# stm8-hid.net
KiCad netlist of a schematic drawn in EAGLE
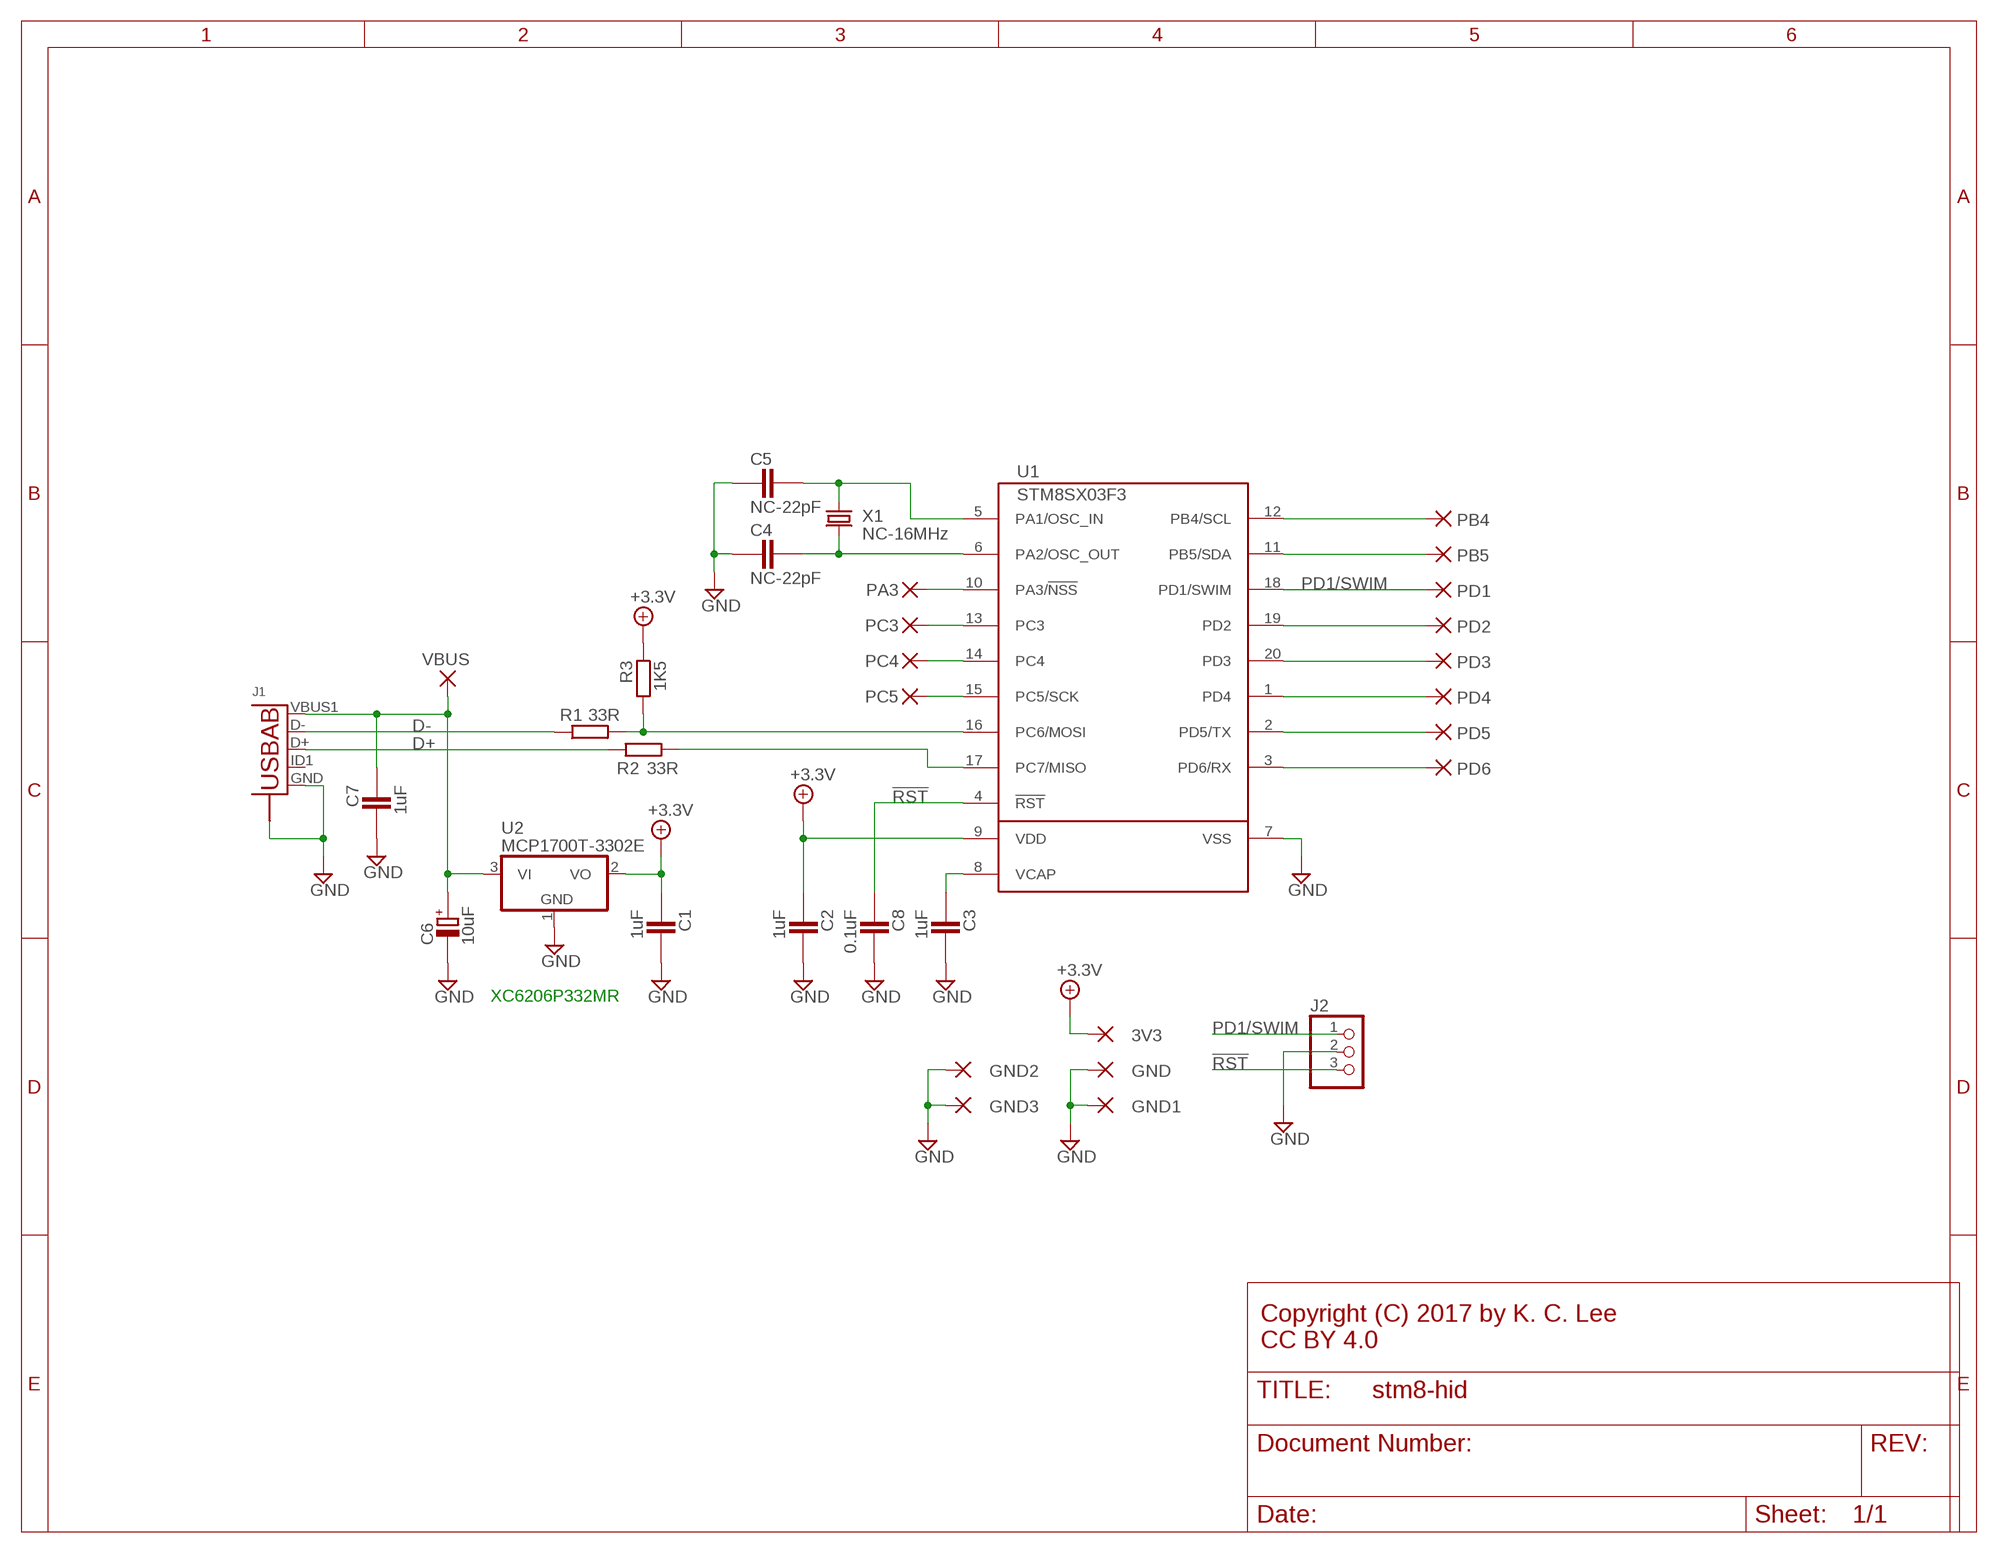
[diagram p0: schematic, sheet 1]

(export (version "E")
  (design (tool "Eeschema 10.0.6"))
  (components
    (comp (ref "3V3")
      (value "SMD2")
      (footprint "eagle-import:SMD1,27-2,54")
      (libsource (lib "eagle-import") (part "SMD2"))
    )
    (comp (ref "C1")
      (value "1uF")
      (footprint "eagle-import:CAPC1608X92N")
      (fields (field (name "PARTNO") "1uF X7R 0603"))
      (libsource (lib "eagle-import") (part "CAPACITOR_0603"))
    )
    (comp (ref "C2")
      (value "1uF")
      (footprint "eagle-import:CAPC1608X92N")
      (fields (field (name "PARTNO") "1uF X7R 0603"))
      (libsource (lib "eagle-import") (part "CAPACITOR_0603"))
    )
    (comp (ref "C3")
      (value "1uF")
      (footprint "eagle-import:CAPC1608X92N")
      (fields (field (name "PARTNO") "1uF X7R 0603"))
      (libsource (lib "eagle-import") (part "CAPACITOR_0603"))
    )
    (comp (ref "C4")
      (value "NC-22pF")
      (footprint "eagle-import:CAPC1608X92N")
      (fields (field (name "PARTNO") "22pF 0603"))
      (libsource (lib "eagle-import") (part "CAPACITOR_0603"))
    )
    (comp (ref "C5")
      (value "NC-22pF")
      (footprint "eagle-import:CAPC1608X92N")
      (fields (field (name "PARTNO") "22pF 0603"))
      (libsource (lib "eagle-import") (part "CAPACITOR_0603"))
    )
    (comp (ref "C6")
      (value "10uF")
      (footprint "eagle-import:CAPMP6032X280N")
      (fields (field (name "PARTNO") "1uF X7R 0603"))
      (libsource (lib "eagle-import") (part "POLARISED_C_CASE"))
    )
    (comp (ref "C7")
      (value "1uF")
      (footprint "eagle-import:CAPC1608X92N")
      (fields (field (name "PARTNO") "NC 0805"))
      (libsource (lib "eagle-import") (part "CAPACITOR_0603"))
    )
    (comp (ref "C8")
      (value "0.1uF")
      (footprint "eagle-import:CAPC1608X92N")
      (fields (field (name "PARTNO") "1uF X7R 0603"))
      (libsource (lib "eagle-import") (part "CAPACITOR_0603"))
    )
    (comp (ref "GND")
      (value "SMD2")
      (footprint "eagle-import:SMD1,27-2,54")
      (libsource (lib "eagle-import") (part "SMD2"))
    )
    (comp (ref "GND1")
      (value "SMD2")
      (footprint "eagle-import:SMD1,27-2,54")
      (libsource (lib "eagle-import") (part "SMD2"))
    )
    (comp (ref "GND2")
      (value "SMD2")
      (footprint "eagle-import:SMD1,27-2,54")
      (libsource (lib "eagle-import") (part "SMD2"))
    )
    (comp (ref "GND3")
      (value "SMD2")
      (footprint "eagle-import:SMD1,27-2,54")
      (libsource (lib "eagle-import") (part "SMD2"))
    )
    (comp (ref "J1")
      (value "USB-ABBG-ORG")
      (footprint "eagle-import:USB-AB-MICRO-SMD_V03_SMT")
      (libsource (lib "eagle-import") (part "USB-ABBG-ORG"))
    )
    (comp (ref "J2")
      (value "PINHD-1X3_2.54")
      (footprint "eagle-import:1X03")
      (libsource (lib "eagle-import") (part "PINHD-1X3_2.54"))
    )
    (comp (ref "PA3")
      (value "SMD2")
      (footprint "eagle-import:SMD1,27-2,54")
      (libsource (lib "eagle-import") (part "SMD2"))
    )
    (comp (ref "PB4")
      (value "SMD2")
      (footprint "eagle-import:SMD1,27-2,54")
      (libsource (lib "eagle-import") (part "SMD2"))
    )
    (comp (ref "PB5")
      (value "SMD2")
      (footprint "eagle-import:SMD1,27-2,54")
      (libsource (lib "eagle-import") (part "SMD2"))
    )
    (comp (ref "PC3")
      (value "SMD2")
      (footprint "eagle-import:SMD1,27-2,54")
      (libsource (lib "eagle-import") (part "SMD2"))
    )
    (comp (ref "PC4")
      (value "SMD2")
      (footprint "eagle-import:SMD1,27-2,54")
      (libsource (lib "eagle-import") (part "SMD2"))
    )
    (comp (ref "PC5")
      (value "SMD2")
      (footprint "eagle-import:SMD1,27-2,54")
      (libsource (lib "eagle-import") (part "SMD2"))
    )
    (comp (ref "PD1")
      (value "SMD2")
      (footprint "eagle-import:SMD1,27-2,54")
      (libsource (lib "eagle-import") (part "SMD2"))
    )
    (comp (ref "PD2")
      (value "SMD2")
      (footprint "eagle-import:SMD1,27-2,54")
      (libsource (lib "eagle-import") (part "SMD2"))
    )
    (comp (ref "PD3")
      (value "SMD2")
      (footprint "eagle-import:SMD1,27-2,54")
      (libsource (lib "eagle-import") (part "SMD2"))
    )
    (comp (ref "PD4")
      (value "SMD2")
      (footprint "eagle-import:SMD1,27-2,54")
      (libsource (lib "eagle-import") (part "SMD2"))
    )
    (comp (ref "PD5")
      (value "SMD2")
      (footprint "eagle-import:SMD1,27-2,54")
      (libsource (lib "eagle-import") (part "SMD2"))
    )
    (comp (ref "PD6")
      (value "SMD2")
      (footprint "eagle-import:SMD1,27-2,54")
      (libsource (lib "eagle-import") (part "SMD2"))
    )
    (comp (ref "R1")
      (value "33R")
      (footprint "eagle-import:RESC1608X55N")
      (fields (field (name "PARTNO") "47R 0603"))
      (libsource (lib "eagle-import") (part "RESISTOR_0603"))
    )
    (comp (ref "R2")
      (value "33R")
      (footprint "eagle-import:RESC1608X55N")
      (fields (field (name "PARTNO") "47R 0603"))
      (libsource (lib "eagle-import") (part "RESISTOR_0603"))
    )
    (comp (ref "R3")
      (value "1K5")
      (footprint "eagle-import:RESC1608X55N")
      (fields (field (name "PARTNO") "1K5 0603"))
      (libsource (lib "eagle-import") (part "RESISTOR_0603"))
    )
    (comp (ref "U1")
      (value "STM8SX03F3")
      (footprint "eagle-import:TSSOP20")
      (libsource (lib "eagle-import") (part "STM8SX03F3"))
    )
    (comp (ref "U2")
      (value "MCP1700T-3302E")
      (footprint "eagle-import:SOT95P280X135-3N")
      (fields (field (name "PARTNO") "MCP1700T-3302E/TT"))
      (libsource (lib "eagle-import") (part "MCP1700/TT"))
    )
    (comp (ref "VBUS")
      (value "SMD2")
      (footprint "eagle-import:SMD1,27-2,54")
      (fields (field (name "PARTNO") "Breakout"))
      (libsource (lib "eagle-import") (part "SMD2"))
    )
    (comp (ref "X1")
      (value "NC-16MHz")
      (footprint "eagle-import:TC38H")
      (fields (field (name "PARTNO") "16MHz Crystal TC26"))
      (libsource (lib "eagle-import") (part "XTAL_SMT"))
    )
  )
  (nets
    (net (code "1") (name "+3.3V") (class "Default")
      (node (ref "3V3") (pin "1") (pinfunction "P_1") (pintype "passive"))
      (node (ref "C1") (pin "1") (pinfunction "1_1") (pintype "passive"))
      (node (ref "C2") (pin "1") (pinfunction "1_1") (pintype "passive"))
      (node (ref "R3") (pin "1") (pinfunction "1_1") (pintype "passive"))
      (node (ref "U1") (pin "9") (pinfunction "VDD_9") (pintype "input"))
      (node (ref "U2") (pin "2") (pinfunction "VO_2") (pintype "passive"))
    )
    (net (code "2") (name "/D+") (class "Default")
      (node (ref "J1") (pin "D+") (pinfunction "D+_D+") (pintype "bidirectional"))
      (node (ref "R2") (pin "1") (pinfunction "1_1") (pintype "passive"))
    )
    (net (code "3") (name "/D-") (class "Default")
      (node (ref "J1") (pin "D-") (pinfunction "D-_D-") (pintype "bidirectional"))
      (node (ref "R1") (pin "1") (pinfunction "1_1") (pintype "passive"))
    )
    (net (code "4") (name "/PD1{slash}SWIM") (class "Default")
      (node (ref "J2") (pin "1") (pinfunction "1_1") (pintype "passive"))
      (node (ref "PD1") (pin "1") (pinfunction "P_1") (pintype "passive"))
      (node (ref "U1") (pin "18") (pinfunction "PD1/SWIM_18") (pintype "input"))
    )
    (net (code "5") (name "/~{RST}") (class "Default")
      (node (ref "C8") (pin "1") (pinfunction "1_1") (pintype "passive"))
      (node (ref "J2") (pin "3") (pinfunction "3_3") (pintype "passive"))
      (node (ref "U1") (pin "4") (pinfunction "~{RST}_4") (pintype "input"))
    )
    (net (code "6") (name "GND") (class "Default")
      (node (ref "C1") (pin "2") (pinfunction "2_2") (pintype "passive"))
      (node (ref "C2") (pin "2") (pinfunction "2_2") (pintype "passive"))
      (node (ref "C3") (pin "2") (pinfunction "2_2") (pintype "passive"))
      (node (ref "C4") (pin "1") (pinfunction "1_1") (pintype "passive"))
      (node (ref "C5") (pin "1") (pinfunction "1_1") (pintype "passive"))
      (node (ref "C6") (pin "-") (pinfunction "-_-") (pintype "passive"))
      (node (ref "C7") (pin "2") (pinfunction "2_2") (pintype "passive"))
      (node (ref "C8") (pin "2") (pinfunction "2_2") (pintype "passive"))
      (node (ref "GND") (pin "1") (pinfunction "P_1") (pintype "passive"))
      (node (ref "GND1") (pin "1") (pinfunction "P_1") (pintype "passive"))
      (node (ref "GND2") (pin "1") (pinfunction "P_1") (pintype "passive"))
      (node (ref "GND3") (pin "1") (pinfunction "P_1") (pintype "passive"))
      (node (ref "J1") (pin "GND") (pinfunction "GND_GND") (pintype "bidirectional"))
      (node (ref "J1") (pin "S1") (pinfunction "S_S1") (pintype "bidirectional"))
      (node (ref "J1") (pin "S2") (pinfunction "S_S2") (pintype "bidirectional"))
      (node (ref "J1") (pin "S3") (pinfunction "S_S3") (pintype "bidirectional"))
      (node (ref "J1") (pin "S4") (pinfunction "S_S4") (pintype "bidirectional"))
      (node (ref "J2") (pin "2") (pinfunction "2_2") (pintype "passive"))
      (node (ref "U1") (pin "7") (pinfunction "VSS_7") (pintype "input"))
      (node (ref "U2") (pin "1") (pinfunction "GND_1") (pintype "passive"))
    )
    (net (code "7") (name "Net-(J1-VBUS)") (class "Default")
      (node (ref "C6") (pin "+") (pinfunction "+_+") (pintype "passive"))
      (node (ref "C7") (pin "1") (pinfunction "1_1") (pintype "passive"))
      (node (ref "J1") (pin "VBUS1") (pinfunction "VBUS_VBUS1") (pintype "bidirectional"))
      (node (ref "U2") (pin "3") (pinfunction "VI_3") (pintype "input"))
      (node (ref "VBUS") (pin "1") (pinfunction "P_1") (pintype "passive"))
    )
    (net (code "8") (name "Net-(PA3-P)") (class "Default")
      (node (ref "PA3") (pin "1") (pinfunction "P_1") (pintype "passive"))
      (node (ref "U1") (pin "10") (pinfunction "PA3/~{NSS}_10") (pintype "bidirectional"))
    )
    (net (code "9") (name "Net-(PB4-P)") (class "Default")
      (node (ref "PB4") (pin "1") (pinfunction "P_1") (pintype "passive"))
      (node (ref "U1") (pin "12") (pinfunction "PB4/SCL_12") (pintype "bidirectional"))
    )
    (net (code "10") (name "Net-(PB5-P)") (class "Default")
      (node (ref "PB5") (pin "1") (pinfunction "P_1") (pintype "passive"))
      (node (ref "U1") (pin "11") (pinfunction "PB5/SDA_11") (pintype "bidirectional"))
    )
    (net (code "11") (name "Net-(PC3-P)") (class "Default")
      (node (ref "PC3") (pin "1") (pinfunction "P_1") (pintype "passive"))
      (node (ref "U1") (pin "13") (pinfunction "PC3_13") (pintype "bidirectional"))
    )
    (net (code "12") (name "Net-(PC4-P)") (class "Default")
      (node (ref "PC4") (pin "1") (pinfunction "P_1") (pintype "passive"))
      (node (ref "U1") (pin "14") (pinfunction "PC4_14") (pintype "bidirectional"))
    )
    (net (code "13") (name "Net-(PC5-P)") (class "Default")
      (node (ref "PC5") (pin "1") (pinfunction "P_1") (pintype "passive"))
      (node (ref "U1") (pin "15") (pinfunction "PC5/SCK_15") (pintype "bidirectional"))
    )
    (net (code "14") (name "Net-(PD2-P)") (class "Default")
      (node (ref "PD2") (pin "1") (pinfunction "P_1") (pintype "passive"))
      (node (ref "U1") (pin "19") (pinfunction "PD2_19") (pintype "bidirectional"))
    )
    (net (code "15") (name "Net-(PD3-P)") (class "Default")
      (node (ref "PD3") (pin "1") (pinfunction "P_1") (pintype "passive"))
      (node (ref "U1") (pin "20") (pinfunction "PD3_20") (pintype "bidirectional"))
    )
    (net (code "16") (name "Net-(PD4-P)") (class "Default")
      (node (ref "PD4") (pin "1") (pinfunction "P_1") (pintype "passive"))
      (node (ref "U1") (pin "1") (pinfunction "PD4_1") (pintype "bidirectional"))
    )
    (net (code "17") (name "Net-(PD5-P)") (class "Default")
      (node (ref "PD5") (pin "1") (pinfunction "P_1") (pintype "passive"))
      (node (ref "U1") (pin "2") (pinfunction "PD5/TX_2") (pintype "bidirectional"))
    )
    (net (code "18") (name "Net-(PD6-P)") (class "Default")
      (node (ref "PD6") (pin "1") (pinfunction "P_1") (pintype "passive"))
      (node (ref "U1") (pin "3") (pinfunction "PD6/RX_3") (pintype "bidirectional"))
    )
    (net (code "19") (name "Net-(U1-PA1{slash}OSC_IN)") (class "Default")
      (node (ref "C5") (pin "2") (pinfunction "2_2") (pintype "passive"))
      (node (ref "U1") (pin "5") (pinfunction "PA1/OSC_IN_5") (pintype "input"))
      (node (ref "X1") (pin "1") (pinfunction "1_1") (pintype "passive"))
    )
    (net (code "20") (name "Net-(U1-PA2{slash}OSC_OUT)") (class "Default")
      (node (ref "C4") (pin "2") (pinfunction "2_2") (pintype "passive"))
      (node (ref "U1") (pin "6") (pinfunction "PA2/OSC_OUT_6") (pintype "output"))
      (node (ref "X1") (pin "2") (pinfunction "2_2") (pintype "passive"))
    )
    (net (code "21") (name "Net-(U1-PC6{slash}MOSI)") (class "Default")
      (node (ref "R1") (pin "2") (pinfunction "2_2") (pintype "passive"))
      (node (ref "R3") (pin "2") (pinfunction "2_2") (pintype "passive"))
      (node (ref "U1") (pin "16") (pinfunction "PC6/MOSI_16") (pintype "bidirectional"))
    )
    (net (code "22") (name "Net-(U1-PC7{slash}MISO)") (class "Default")
      (node (ref "R2") (pin "2") (pinfunction "2_2") (pintype "passive"))
      (node (ref "U1") (pin "17") (pinfunction "PC7/MISO_17") (pintype "bidirectional"))
    )
    (net (code "23") (name "Net-(U1-VCAP)") (class "Default")
      (node (ref "C3") (pin "1") (pinfunction "1_1") (pintype "passive"))
      (node (ref "U1") (pin "8") (pinfunction "VCAP_8") (pintype "input"))
    )
    (net (code "24") (name "unconnected-(J1-USBID-PadID1)") (class "Default")
      (node (ref "J1") (pin "ID1") (pinfunction "USBID_ID1") (pintype "bidirectional"))
    )
  )
)
